# Codeshelf-0009_v02.net
KiCad netlist of a schematic drawn in EAGLE
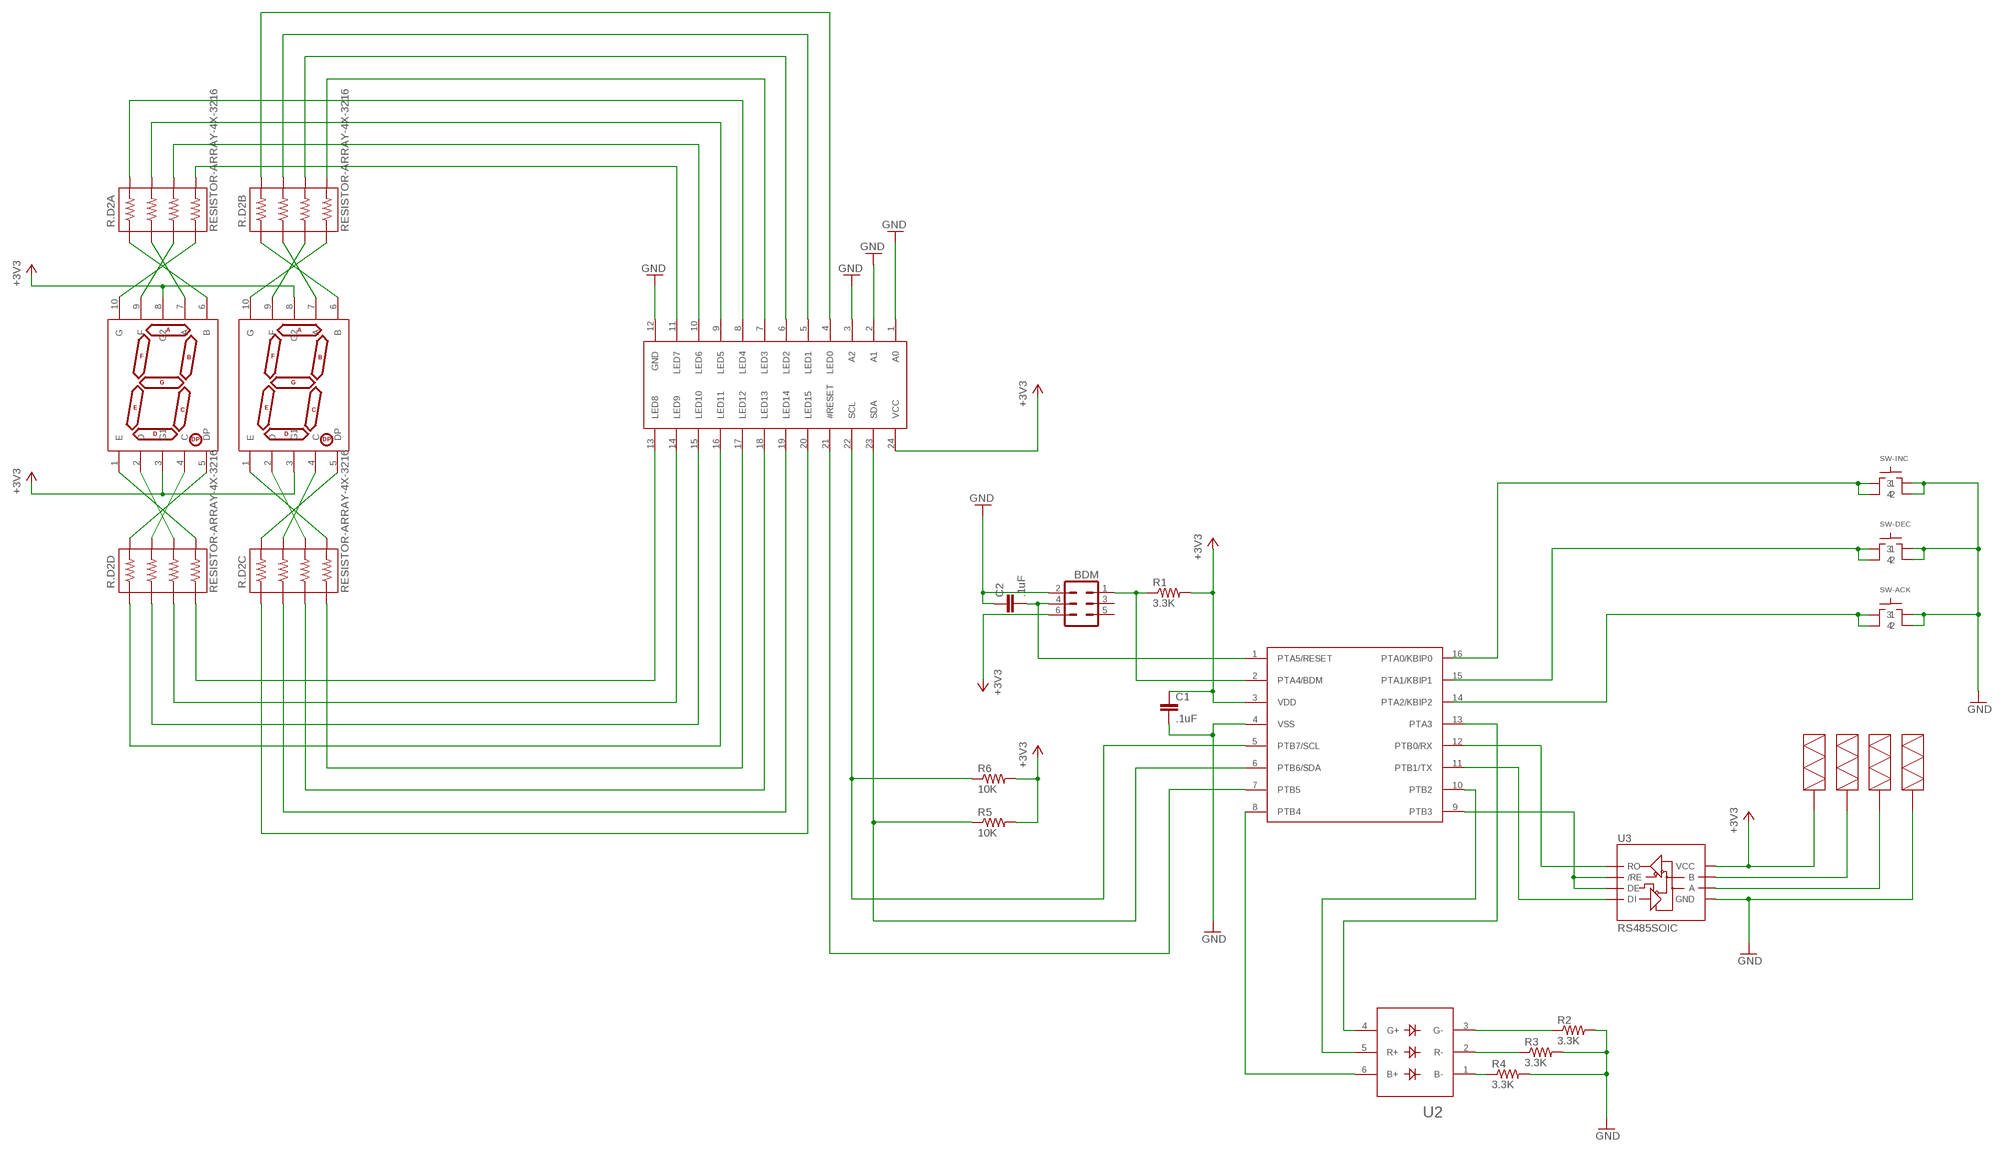
[diagram p0: schematic, sheet 1]

(export (version "E")
  (design (tool "Eeschema 10.0.6"))
  (components
    (comp (ref "BDM")
      (value "HEADER-3X2")
      (footprint "eagle-import:HEADER-3X2")
      (libsource (lib "eagle-import") (part "HEADER-3X2"))
    )
    (comp (ref "C1")
      (value ".1uF")
      (footprint "eagle-import:C0402")
      (libsource (lib "eagle-import") (part "RF-C0402"))
    )
    (comp (ref "C2")
      (value ".1uF")
      (footprint "eagle-import:C0402")
      (libsource (lib "eagle-import") (part "RF-C0402"))
    )
    (comp (ref "J1")
      (value "CONTACT-SPRING-S7071-42R")
      (footprint "eagle-import:CONTACT-SPRING-S1761")
      (libsource (lib "eagle-import") (part "CONTACT-SPRING-S1761"))
    )
    (comp (ref "J2")
      (value "CONTACT-SPRING-S7071-42R")
      (footprint "eagle-import:CONTACT-SPRING-S1761")
      (libsource (lib "eagle-import") (part "CONTACT-SPRING-S1761"))
    )
    (comp (ref "J3")
      (value "CONTACT-SPRING-S7071-42R")
      (footprint "eagle-import:CONTACT-SPRING-S1761")
      (libsource (lib "eagle-import") (part "CONTACT-SPRING-S1761"))
    )
    (comp (ref "J4")
      (value "CONTACT-SPRING-S7071-42R")
      (footprint "eagle-import:CONTACT-SPRING-S1761")
      (libsource (lib "eagle-import") (part "CONTACT-SPRING-S1761"))
    )
    (comp (ref "LED1")
      (value "7SEGMENT-1DIGITSMD")
      (footprint "eagle-import:7SEGMENT-1DIG-.40-SMD")
      (libsource (lib "eagle-import") (part "7SEGMENT-1DIGITSMD"))
    )
    (comp (ref "LED2")
      (value "7SEGMENT-1DIGITSMD")
      (footprint "eagle-import:7SEGMENT-1DIG-.40-SMD")
      (libsource (lib "eagle-import") (part "7SEGMENT-1DIGITSMD"))
    )
    (comp (ref "R.D2A")
      (value "RESISTOR-ARRAY-4X-3216")
      (footprint "eagle-import:3216-4X")
      (libsource (lib "eagle-import") (part "RESISTOR-ARRAY-4X-3216"))
    )
    (comp (ref "R.D2B")
      (value "RESISTOR-ARRAY-4X-3216")
      (footprint "eagle-import:3216-4X")
      (libsource (lib "eagle-import") (part "RESISTOR-ARRAY-4X-3216"))
    )
    (comp (ref "R.D2C")
      (value "RESISTOR-ARRAY-4X-3216")
      (footprint "eagle-import:3216-4X")
      (libsource (lib "eagle-import") (part "RESISTOR-ARRAY-4X-3216"))
    )
    (comp (ref "R.D2D")
      (value "RESISTOR-ARRAY-4X-3216")
      (footprint "eagle-import:3216-4X")
      (libsource (lib "eagle-import") (part "RESISTOR-ARRAY-4X-3216"))
    )
    (comp (ref "R1")
      (value "3.3K")
      (footprint "eagle-import:RF-R0402")
      (libsource (lib "eagle-import") (part "RF-R0402"))
    )
    (comp (ref "R2")
      (value "3.3K")
      (footprint "eagle-import:RF-R0402")
      (libsource (lib "eagle-import") (part "RF-R0402"))
    )
    (comp (ref "R3")
      (value "3.3K")
      (footprint "eagle-import:RF-R0402")
      (libsource (lib "eagle-import") (part "RF-R0402"))
    )
    (comp (ref "R4")
      (value "3.3K")
      (footprint "eagle-import:RF-R0402")
      (libsource (lib "eagle-import") (part "RF-R0402"))
    )
    (comp (ref "R5")
      (value "10K")
      (footprint "eagle-import:RF-R0402")
      (libsource (lib "eagle-import") (part "RF-R0402"))
    )
    (comp (ref "R6")
      (value "10K")
      (footprint "eagle-import:RF-R0402")
      (libsource (lib "eagle-import") (part "RF-R0402"))
    )
    (comp (ref "SW-ACK")
      (value "SWITCH-TACTILE-320.03E11")
      (footprint "eagle-import:SWITCH-TACTILE-320.03E11")
      (libsource (lib "eagle-import") (part "SWITCH-TACTILE-320.03E11"))
    )
    (comp (ref "SW-DEC")
      (value "SWITCH-TACTILE-FSM")
      (footprint "eagle-import:SWITCH-TACTILE-FSM")
      (libsource (lib "eagle-import") (part "SWITCH-TACTILE-FSM"))
    )
    (comp (ref "SW-INC")
      (value "SWITCH-TACTILE-FSM")
      (footprint "eagle-import:SWITCH-TACTILE-FSM")
      (libsource (lib "eagle-import") (part "SWITCH-TACTILE-FSM"))
    )
    (comp (ref "U1")
      (value "MC9S08QG-DT")
      (footprint "eagle-import:TSSOP16")
      (libsource (lib "eagle-import") (part "MC9S08QG-DT"))
    )
    (comp (ref "U2")
      (value "LED5060A")
      (footprint "eagle-import:PLCC-6")
      (libsource (lib "eagle-import") (part "LED5060A"))
    )
    (comp (ref "U3")
      (value "RS485SOIC")
      (footprint "eagle-import:SO08")
      (libsource (lib "eagle-import") (part "RS485SOIC"))
    )
    (comp (ref "U4")
      (value "CAT9552")
      (footprint "eagle-import:TSSOP24")
      (libsource (lib "eagle-import") (part "CAT9552"))
    )
  )
  (nets
    (net (code "1") (name "+3V3") (class "Default")
      (node (ref "BDM") (pin "6") (pinfunction "6_6") (pintype "passive"))
      (node (ref "C1") (pin "1") (pinfunction "1_1") (pintype "passive"))
      (node (ref "J1") (pin "P1") (pinfunction "P1_P1") (pintype "bidirectional"))
      (node (ref "LED1") (pin "3") (pinfunction "G1_3") (pintype "bidirectional"))
      (node (ref "LED1") (pin "8") (pinfunction "G2_8") (pintype "bidirectional"))
      (node (ref "LED2") (pin "3") (pinfunction "G1_3") (pintype "bidirectional"))
      (node (ref "LED2") (pin "8") (pinfunction "G2_8") (pintype "bidirectional"))
      (node (ref "R1") (pin "2") (pinfunction "2_2") (pintype "passive"))
      (node (ref "R5") (pin "2") (pinfunction "2_2") (pintype "passive"))
      (node (ref "R6") (pin "2") (pinfunction "2_2") (pintype "passive"))
      (node (ref "U1") (pin "3") (pinfunction "VDD_3") (pintype "bidirectional"))
      (node (ref "U3") (pin "8") (pinfunction "VCC_8") (pintype "bidirectional"))
      (node (ref "U4") (pin "24") (pinfunction "VCC_24") (pintype "bidirectional"))
    )
    (net (code "2") (name "GND") (class "Default")
      (node (ref "BDM") (pin "2") (pinfunction "2_2") (pintype "passive"))
      (node (ref "C1") (pin "2") (pinfunction "2_2") (pintype "passive"))
      (node (ref "C2") (pin "1") (pinfunction "1_1") (pintype "passive"))
      (node (ref "J4") (pin "P1") (pinfunction "P1_P1") (pintype "bidirectional"))
      (node (ref "R2") (pin "2") (pinfunction "2_2") (pintype "passive"))
      (node (ref "R3") (pin "2") (pinfunction "2_2") (pintype "passive"))
      (node (ref "R4") (pin "2") (pinfunction "2_2") (pintype "passive"))
      (node (ref "SW-ACK") (pin "P$3") (pinfunction "3_P$3") (pintype "input"))
      (node (ref "SW-ACK") (pin "P$4") (pinfunction "4_P$4") (pintype "input"))
      (node (ref "SW-DEC") (pin "P$3") (pinfunction "3_P$3") (pintype "input"))
      (node (ref "SW-DEC") (pin "P$4") (pinfunction "4_P$4") (pintype "input"))
      (node (ref "SW-INC") (pin "P$3") (pinfunction "3_P$3") (pintype "input"))
      (node (ref "SW-INC") (pin "P$4") (pinfunction "4_P$4") (pintype "input"))
      (node (ref "U1") (pin "4") (pinfunction "VSS_4") (pintype "bidirectional"))
      (node (ref "U3") (pin "5") (pinfunction "GND_5") (pintype "bidirectional"))
      (node (ref "U4") (pin "1") (pinfunction "A0_1") (pintype "bidirectional"))
      (node (ref "U4") (pin "12") (pinfunction "GND_12") (pintype "bidirectional"))
      (node (ref "U4") (pin "2") (pinfunction "A1_2") (pintype "bidirectional"))
      (node (ref "U4") (pin "3") (pinfunction "A2_3") (pintype "bidirectional"))
    )
    (net (code "3") (name "Net-(LED1-A)") (class "Default")
      (node (ref "LED1") (pin "7") (pinfunction "A_7") (pintype "bidirectional"))
      (node (ref "R.D2B") (pin "2") (pinfunction "2A_2") (pintype "passive"))
    )
    (net (code "4") (name "Net-(LED1-B)") (class "Default")
      (node (ref "LED1") (pin "6") (pinfunction "B_6") (pintype "bidirectional"))
      (node (ref "R.D2B") (pin "1") (pinfunction "1A_1") (pintype "passive"))
    )
    (net (code "5") (name "Net-(LED1-C)") (class "Default")
      (node (ref "LED1") (pin "4") (pinfunction "C_4") (pintype "bidirectional"))
      (node (ref "R.D2C") (pin "7") (pinfunction "2B_7") (pintype "passive"))
    )
    (net (code "6") (name "Net-(LED1-D)") (class "Default")
      (node (ref "LED1") (pin "2") (pinfunction "D_2") (pintype "bidirectional"))
      (node (ref "R.D2C") (pin "6") (pinfunction "3B_6") (pintype "passive"))
    )
    (net (code "7") (name "Net-(LED1-DP)") (class "Default")
      (node (ref "LED1") (pin "5") (pinfunction "DP_5") (pintype "bidirectional"))
      (node (ref "R.D2C") (pin "8") (pinfunction "1B_8") (pintype "passive"))
    )
    (net (code "8") (name "Net-(LED1-E)") (class "Default")
      (node (ref "LED1") (pin "1") (pinfunction "E_1") (pintype "bidirectional"))
      (node (ref "R.D2C") (pin "5") (pinfunction "4B_5") (pintype "passive"))
    )
    (net (code "9") (name "Net-(LED1-F)") (class "Default")
      (node (ref "LED1") (pin "9") (pinfunction "F_9") (pintype "bidirectional"))
      (node (ref "R.D2B") (pin "3") (pinfunction "3A_3") (pintype "passive"))
    )
    (net (code "10") (name "Net-(LED1-G)") (class "Default")
      (node (ref "LED1") (pin "10") (pinfunction "G_10") (pintype "bidirectional"))
      (node (ref "R.D2B") (pin "4") (pinfunction "4A_4") (pintype "passive"))
    )
    (net (code "11") (name "Net-(LED2-A)") (class "Default")
      (node (ref "LED2") (pin "7") (pinfunction "A_7") (pintype "bidirectional"))
      (node (ref "R.D2A") (pin "2") (pinfunction "2A_2") (pintype "passive"))
    )
    (net (code "12") (name "Net-(LED2-B)") (class "Default")
      (node (ref "LED2") (pin "6") (pinfunction "B_6") (pintype "bidirectional"))
      (node (ref "R.D2A") (pin "1") (pinfunction "1A_1") (pintype "passive"))
    )
    (net (code "13") (name "Net-(LED2-C)") (class "Default")
      (node (ref "LED2") (pin "4") (pinfunction "C_4") (pintype "bidirectional"))
      (node (ref "R.D2D") (pin "7") (pinfunction "2B_7") (pintype "passive"))
    )
    (net (code "14") (name "Net-(LED2-D)") (class "Default")
      (node (ref "LED2") (pin "2") (pinfunction "D_2") (pintype "bidirectional"))
      (node (ref "R.D2D") (pin "6") (pinfunction "3B_6") (pintype "passive"))
    )
    (net (code "15") (name "Net-(LED2-DP)") (class "Default")
      (node (ref "LED2") (pin "5") (pinfunction "DP_5") (pintype "bidirectional"))
      (node (ref "R.D2D") (pin "8") (pinfunction "1B_8") (pintype "passive"))
    )
    (net (code "16") (name "Net-(LED2-E)") (class "Default")
      (node (ref "LED2") (pin "1") (pinfunction "E_1") (pintype "bidirectional"))
      (node (ref "R.D2D") (pin "5") (pinfunction "4B_5") (pintype "passive"))
    )
    (net (code "17") (name "Net-(LED2-F)") (class "Default")
      (node (ref "LED2") (pin "9") (pinfunction "F_9") (pintype "bidirectional"))
      (node (ref "R.D2A") (pin "3") (pinfunction "3A_3") (pintype "passive"))
    )
    (net (code "18") (name "Net-(LED2-G)") (class "Default")
      (node (ref "LED2") (pin "10") (pinfunction "G_10") (pintype "bidirectional"))
      (node (ref "R.D2A") (pin "4") (pinfunction "4A_4") (pintype "passive"))
    )
    (net (code "19") (name "Net-(R.D2A-1B)") (class "Default")
      (node (ref "R.D2A") (pin "8") (pinfunction "1B_8") (pintype "passive"))
      (node (ref "U4") (pin "8") (pinfunction "LED4_8") (pintype "bidirectional"))
    )
    (net (code "20") (name "Net-(R.D2A-2B)") (class "Default")
      (node (ref "R.D2A") (pin "7") (pinfunction "2B_7") (pintype "passive"))
      (node (ref "U4") (pin "9") (pinfunction "LED5_9") (pintype "bidirectional"))
    )
    (net (code "21") (name "Net-(R.D2A-3B)") (class "Default")
      (node (ref "R.D2A") (pin "6") (pinfunction "3B_6") (pintype "passive"))
      (node (ref "U4") (pin "10") (pinfunction "LED6_10") (pintype "bidirectional"))
    )
    (net (code "22") (name "Net-(R.D2A-4B)") (class "Default")
      (node (ref "R.D2A") (pin "5") (pinfunction "4B_5") (pintype "passive"))
      (node (ref "U4") (pin "11") (pinfunction "LED7_11") (pintype "bidirectional"))
    )
    (net (code "23") (name "Net-(R.D2B-1B)") (class "Default")
      (node (ref "R.D2B") (pin "8") (pinfunction "1B_8") (pintype "passive"))
      (node (ref "U4") (pin "4") (pinfunction "LED0_4") (pintype "bidirectional"))
    )
    (net (code "24") (name "Net-(R.D2B-2B)") (class "Default")
      (node (ref "R.D2B") (pin "7") (pinfunction "2B_7") (pintype "passive"))
      (node (ref "U4") (pin "5") (pinfunction "LED1_5") (pintype "bidirectional"))
    )
    (net (code "25") (name "Net-(R.D2B-3B)") (class "Default")
      (node (ref "R.D2B") (pin "6") (pinfunction "3B_6") (pintype "passive"))
      (node (ref "U4") (pin "6") (pinfunction "LED2_6") (pintype "bidirectional"))
    )
    (net (code "26") (name "Net-(R.D2B-4B)") (class "Default")
      (node (ref "R.D2B") (pin "5") (pinfunction "4B_5") (pintype "passive"))
      (node (ref "U4") (pin "7") (pinfunction "LED3_7") (pintype "bidirectional"))
    )
    (net (code "27") (name "Net-(R.D2C-1A)") (class "Default")
      (node (ref "R.D2C") (pin "1") (pinfunction "1A_1") (pintype "passive"))
      (node (ref "U4") (pin "20") (pinfunction "LED15_20") (pintype "bidirectional"))
    )
    (net (code "28") (name "Net-(R.D2C-2A)") (class "Default")
      (node (ref "R.D2C") (pin "2") (pinfunction "2A_2") (pintype "passive"))
      (node (ref "U4") (pin "19") (pinfunction "LED14_19") (pintype "bidirectional"))
    )
    (net (code "29") (name "Net-(R.D2C-3A)") (class "Default")
      (node (ref "R.D2C") (pin "3") (pinfunction "3A_3") (pintype "passive"))
      (node (ref "U4") (pin "18") (pinfunction "LED13_18") (pintype "bidirectional"))
    )
    (net (code "30") (name "Net-(R.D2C-4A)") (class "Default")
      (node (ref "R.D2C") (pin "4") (pinfunction "4A_4") (pintype "passive"))
      (node (ref "U4") (pin "17") (pinfunction "LED12_17") (pintype "bidirectional"))
    )
    (net (code "31") (name "Net-(R.D2D-1A)") (class "Default")
      (node (ref "R.D2D") (pin "1") (pinfunction "1A_1") (pintype "passive"))
      (node (ref "U4") (pin "16") (pinfunction "LED11_16") (pintype "bidirectional"))
    )
    (net (code "32") (name "Net-(R.D2D-2A)") (class "Default")
      (node (ref "R.D2D") (pin "2") (pinfunction "2A_2") (pintype "passive"))
      (node (ref "U4") (pin "15") (pinfunction "LED10_15") (pintype "bidirectional"))
    )
    (net (code "33") (name "Net-(R.D2D-3A)") (class "Default")
      (node (ref "R.D2D") (pin "3") (pinfunction "3A_3") (pintype "passive"))
      (node (ref "U4") (pin "14") (pinfunction "LED9_14") (pintype "bidirectional"))
    )
    (net (code "34") (name "Net-(R.D2D-4A)") (class "Default")
      (node (ref "R.D2D") (pin "4") (pinfunction "4A_4") (pintype "passive"))
      (node (ref "U4") (pin "13") (pinfunction "LED8_13") (pintype "bidirectional"))
    )
    (net (code "35") (name "Net-(SW-ACK-1)") (class "Default")
      (node (ref "SW-ACK") (pin "P$1") (pinfunction "1_P$1") (pintype "input"))
      (node (ref "SW-ACK") (pin "P$2") (pinfunction "2_P$2") (pintype "input"))
    )
    (net (code "36") (name "Net-(SW-DEC-1)") (class "Default")
      (node (ref "SW-DEC") (pin "P$1") (pinfunction "1_P$1") (pintype "input"))
      (node (ref "SW-DEC") (pin "P$2") (pinfunction "2_P$2") (pintype "input"))
    )
    (net (code "37") (name "Net-(SW-INC-1)") (class "Default")
      (node (ref "SW-INC") (pin "P$1") (pinfunction "1_P$1") (pintype "input"))
      (node (ref "SW-INC") (pin "P$2") (pinfunction "2_P$2") (pintype "input"))
    )
    (net (code "38") (name "Net-(U1-PTA3)") (class "Default")
      (node (ref "U1") (pin "13") (pinfunction "PTA3_13") (pintype "bidirectional"))
      (node (ref "U2") (pin "4") (pinfunction "G+_4") (pintype "bidirectional"))
    )
    (net (code "39") (name "Net-(U1-PTA4{slash}BDM)") (class "Default")
      (node (ref "BDM") (pin "1") (pinfunction "1_1") (pintype "passive"))
      (node (ref "R1") (pin "1") (pinfunction "1_1") (pintype "passive"))
      (node (ref "U1") (pin "2") (pinfunction "PTA4/BDM_2") (pintype "bidirectional"))
    )
    (net (code "40") (name "Net-(U1-PTA5{slash}RESET)") (class "Default")
      (node (ref "BDM") (pin "4") (pinfunction "4_4") (pintype "passive"))
      (node (ref "C2") (pin "2") (pinfunction "2_2") (pintype "passive"))
      (node (ref "U1") (pin "1") (pinfunction "PTA5/RESET_1") (pintype "bidirectional"))
    )
    (net (code "41") (name "Net-(U1-PTB0{slash}RX)") (class "Default")
      (node (ref "U1") (pin "12") (pinfunction "PTB0/RX_12") (pintype "bidirectional"))
      (node (ref "U3") (pin "1") (pinfunction "RO_1") (pintype "bidirectional"))
    )
    (net (code "42") (name "Net-(U1-PTB1{slash}TX)") (class "Default")
      (node (ref "U1") (pin "11") (pinfunction "PTB1/TX_11") (pintype "bidirectional"))
      (node (ref "U3") (pin "4") (pinfunction "DI_4") (pintype "bidirectional"))
    )
    (net (code "43") (name "Net-(U1-PTB2)") (class "Default")
      (node (ref "U1") (pin "10") (pinfunction "PTB2_10") (pintype "bidirectional"))
      (node (ref "U2") (pin "5") (pinfunction "R+_5") (pintype "bidirectional"))
    )
    (net (code "44") (name "Net-(U1-PTB3)") (class "Default")
      (node (ref "U1") (pin "9") (pinfunction "PTB3_9") (pintype "bidirectional"))
      (node (ref "U3") (pin "2") (pinfunction "/RE_2") (pintype "bidirectional"))
      (node (ref "U3") (pin "3") (pinfunction "DE_3") (pintype "bidirectional"))
    )
    (net (code "45") (name "Net-(U1-PTB4)") (class "Default")
      (node (ref "U1") (pin "8") (pinfunction "PTB4_8") (pintype "bidirectional"))
      (node (ref "U2") (pin "6") (pinfunction "B+_6") (pintype "bidirectional"))
    )
    (net (code "46") (name "Net-(U1-PTB5)") (class "Default")
      (node (ref "U1") (pin "7") (pinfunction "PTB5_7") (pintype "bidirectional"))
      (node (ref "U4") (pin "21") (pinfunction "#RESET_21") (pintype "bidirectional"))
    )
    (net (code "47") (name "Net-(U1-PTB6{slash}SDA)") (class "Default")
      (node (ref "R5") (pin "1") (pinfunction "1_1") (pintype "passive"))
      (node (ref "U1") (pin "6") (pinfunction "PTB6/SDA_6") (pintype "bidirectional"))
      (node (ref "U4") (pin "23") (pinfunction "SDA_23") (pintype "bidirectional"))
    )
    (net (code "48") (name "Net-(U1-PTB7{slash}SCL)") (class "Default")
      (node (ref "R6") (pin "1") (pinfunction "1_1") (pintype "passive"))
      (node (ref "U1") (pin "5") (pinfunction "PTB7/SCL_5") (pintype "bidirectional"))
      (node (ref "U4") (pin "22") (pinfunction "SCL_22") (pintype "bidirectional"))
    )
    (net (code "49") (name "Net-(U2-B-)") (class "Default")
      (node (ref "R4") (pin "1") (pinfunction "1_1") (pintype "passive"))
      (node (ref "U2") (pin "1") (pinfunction "B-_1") (pintype "bidirectional"))
    )
    (net (code "50") (name "Net-(U2-G-)") (class "Default")
      (node (ref "R2") (pin "1") (pinfunction "1_1") (pintype "passive"))
      (node (ref "U2") (pin "3") (pinfunction "G-_3") (pintype "bidirectional"))
    )
    (net (code "51") (name "Net-(U2-R-)") (class "Default")
      (node (ref "R3") (pin "1") (pinfunction "1_1") (pintype "passive"))
      (node (ref "U2") (pin "2") (pinfunction "R-_2") (pintype "bidirectional"))
    )
    (net (code "52") (name "Net-(U3-A)") (class "Default")
      (node (ref "J3") (pin "P1") (pinfunction "P1_P1") (pintype "bidirectional"))
      (node (ref "U3") (pin "6") (pinfunction "A_6") (pintype "bidirectional"))
    )
    (net (code "53") (name "Net-(U3-B)") (class "Default")
      (node (ref "J2") (pin "P1") (pinfunction "P1_P1") (pintype "bidirectional"))
      (node (ref "U3") (pin "7") (pinfunction "B_7") (pintype "bidirectional"))
    )
    (net (code "54") (name "unconnected-(BDM-Pad3)") (class "Default")
      (node (ref "BDM") (pin "3") (pinfunction "3_3") (pintype "passive"))
    )
    (net (code "55") (name "unconnected-(BDM-Pad5)") (class "Default")
      (node (ref "BDM") (pin "5") (pinfunction "5_5") (pintype "passive"))
    )
    (net (code "56") (name "unconnected-(U1-PTA0{slash}KBIP0-Pad16)") (class "Default")
      (node (ref "U1") (pin "16") (pinfunction "PTA0/KBIP0_16") (pintype "bidirectional"))
    )
    (net (code "57") (name "unconnected-(U1-PTA1{slash}KBIP1-Pad15)") (class "Default")
      (node (ref "U1") (pin "15") (pinfunction "PTA1/KBIP1_15") (pintype "bidirectional"))
    )
    (net (code "58") (name "unconnected-(U1-PTA2{slash}KBIP2-Pad14)") (class "Default")
      (node (ref "U1") (pin "14") (pinfunction "PTA2/KBIP2_14") (pintype "bidirectional"))
    )
  )
)
